# Sheet3.net
KiCad netlist of a schematic drawn in Altium Designer
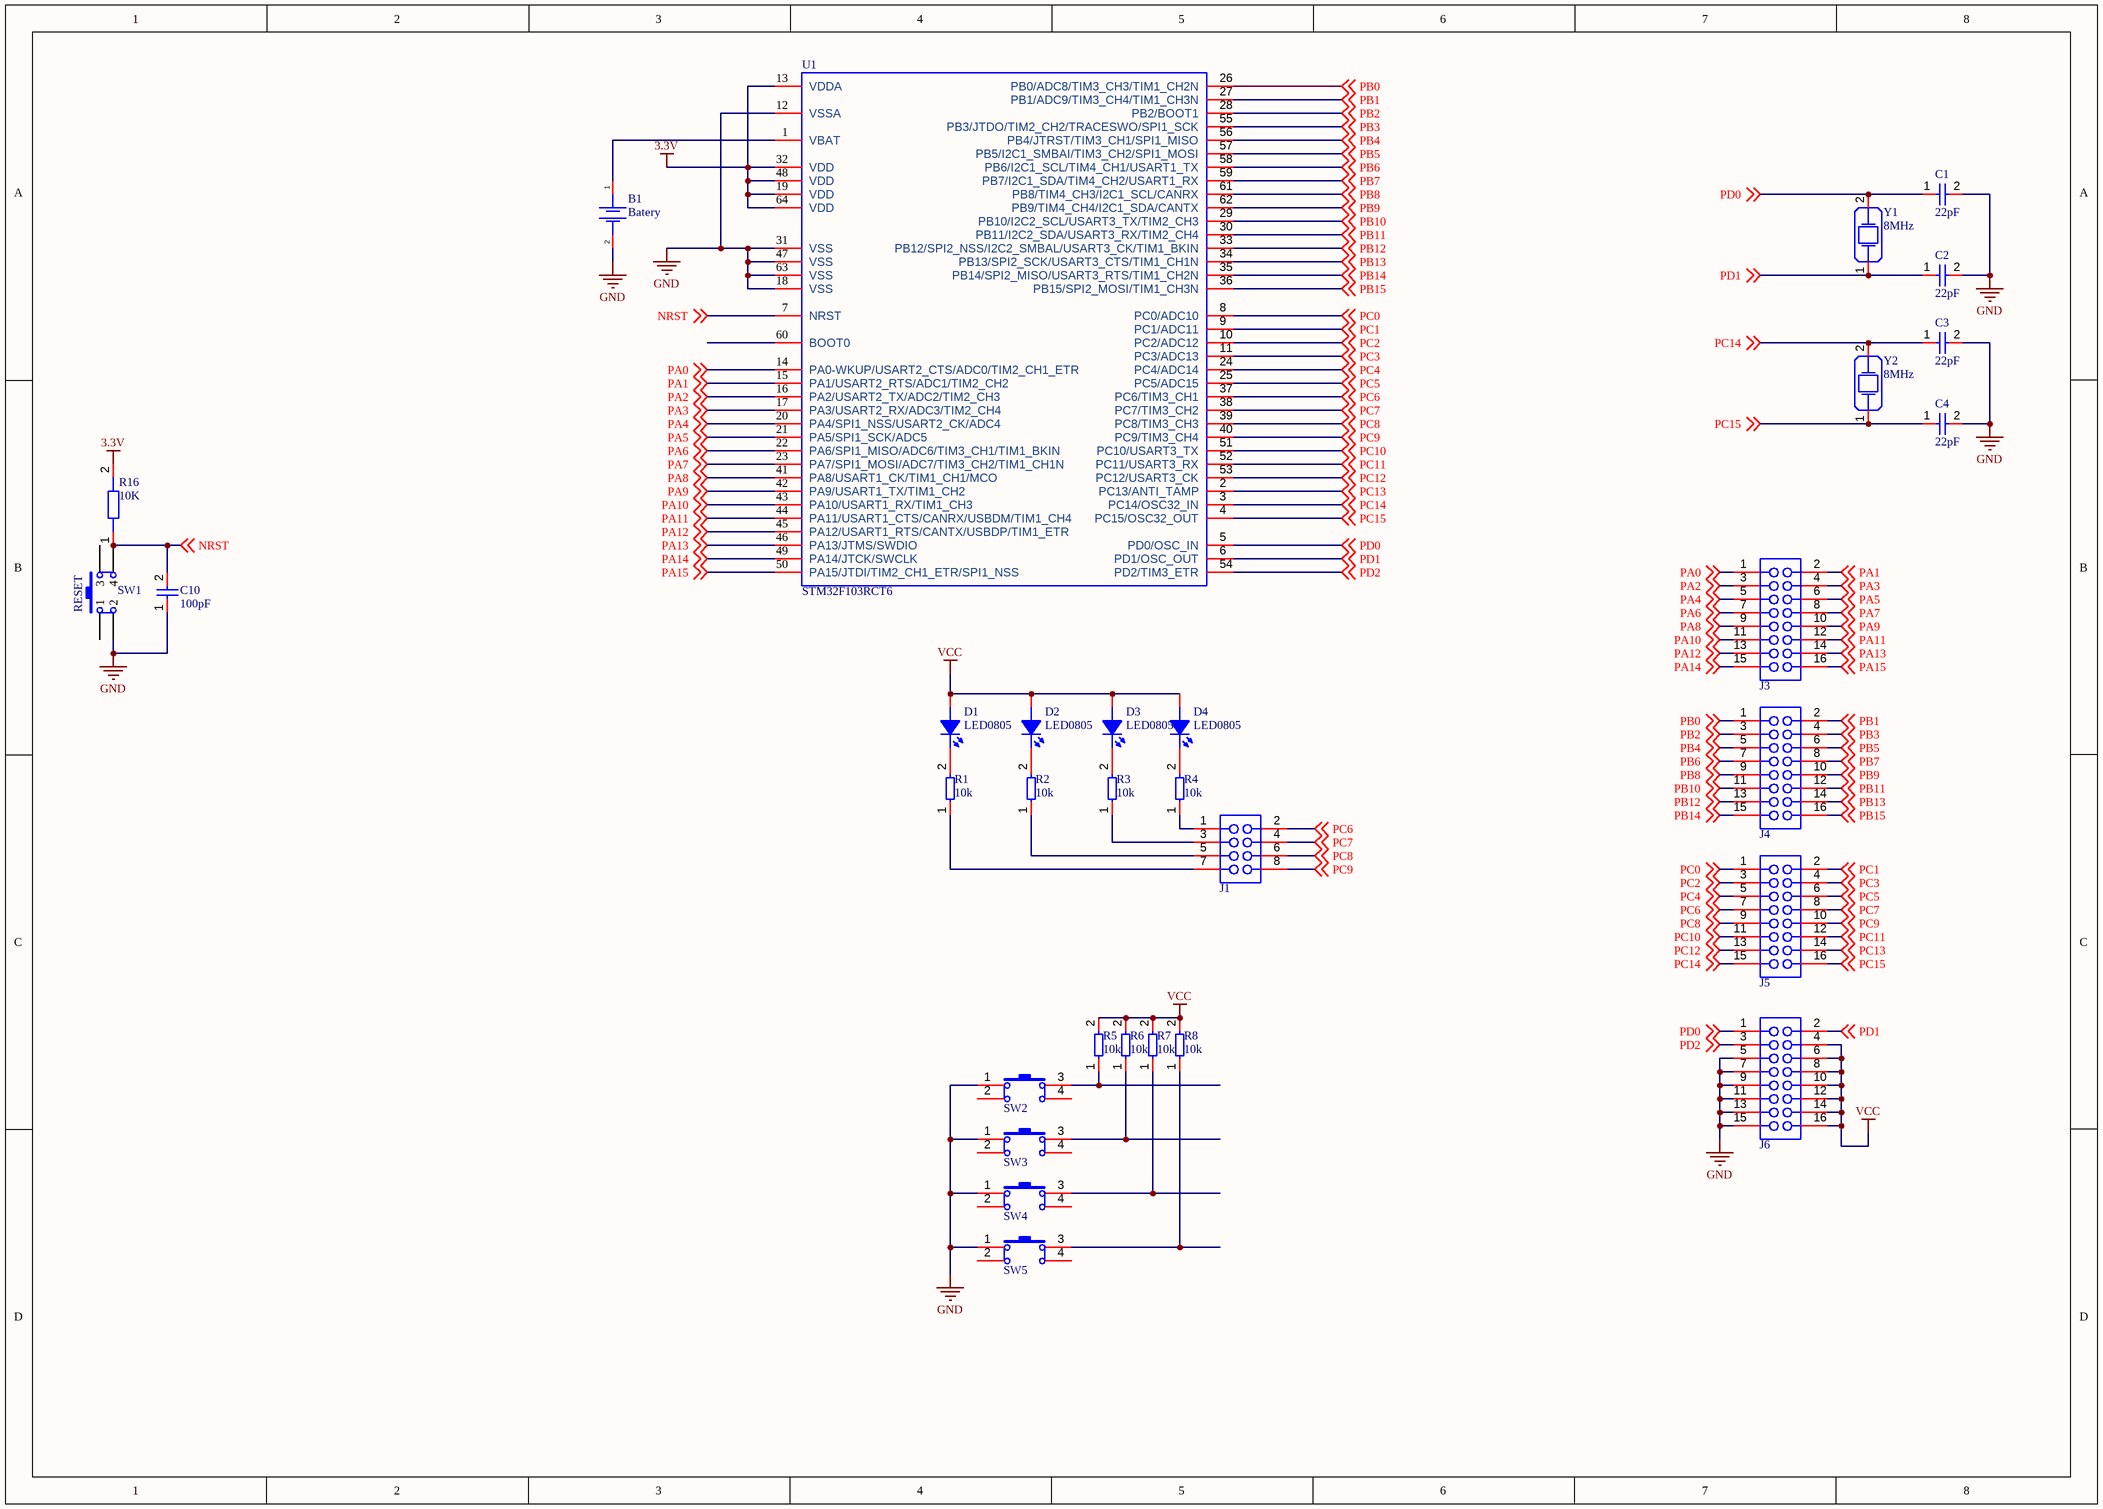
[diagram p0: Sheet3.SchDoc]

(export (version "E")
  (design (tool "Eeschema 10.0.6"))
  (components
    (comp (ref "B1") (value "Batery") (footprint "CR1220") (libsource (lib "SMDLibrary") (part "Batery")))
    (comp (ref "C1")
      (value "22pF")
      (footprint "C0805")
      (libsource (lib "SMDLibrary") (part "Capacitors(SMD)"))
    )
    (comp (ref "C2")
      (value "22pF")
      (footprint "C0805")
      (libsource (lib "SMDLibrary") (part "Capacitors(SMD)"))
    )
    (comp (ref "C3")
      (value "22pF")
      (footprint "C0805")
      (libsource (lib "SMDLibrary") (part "Capacitors(SMD)"))
    )
    (comp (ref "C4")
      (value "22pF")
      (footprint "C0805")
      (libsource (lib "SMDLibrary") (part "Capacitors(SMD)"))
    )
    (comp (ref "C10")
      (value "100pF")
      (footprint "CAP_DISC_PITCH_2.54MM")
      (libsource (lib "SMDLibrary") (part "Capacitors(Disc)"))
    )
    (comp (ref "D1") (value "LED0805") (footprint "L0805RED") (libsource (lib "SMDLibrary") (part "LED0805")))
    (comp (ref "D2") (value "LED0805") (footprint "L0805RED") (libsource (lib "SMDLibrary") (part "LED0805")))
    (comp (ref "D3") (value "LED0805") (footprint "L0805RED") (libsource (lib "SMDLibrary") (part "LED0805")))
    (comp (ref "D4") (value "LED0805") (footprint "L0805RED") (libsource (lib "SMDLibrary") (part "LED0805")))
    (comp (ref "J1")
      (value "Header 4x2 TH Pitch 2.54mm")
      (footprint "Header 4x2 TH Pitch 2.54mm")
      (libsource (lib "SMDLibrary") (part "Header 4x2 TH Pitch 2.54mm"))
    )
    (comp (ref "J3")
      (value "Header 8x2 TH Pitch 2.54mm")
      (footprint "Header 8x2 TH Pitch 2.54mm")
      (libsource (lib "SMDLibrary") (part "Header 8x2 TH Pitch 2.54mm"))
    )
    (comp (ref "J4")
      (value "Header 8x2 TH Pitch 2.54mm")
      (footprint "Header 8x2 TH Pitch 2.54mm")
      (libsource (lib "SMDLibrary") (part "Header 8x2 TH Pitch 2.54mm"))
    )
    (comp (ref "J5")
      (value "Header 8x2 TH Pitch 2.54mm")
      (footprint "Header 8x2 TH Pitch 2.54mm")
      (libsource (lib "SMDLibrary") (part "Header 8x2 TH Pitch 2.54mm"))
    )
    (comp (ref "J6")
      (value "Header 8x2 TH Pitch 2.54mm")
      (footprint "Header 8x2 TH Pitch 2.54mm")
      (libsource (lib "SMDLibrary") (part "Header 8x2 TH Pitch 2.54mm"))
    )
    (comp (ref "R1") (value "10k") (footprint "R0805") (libsource (lib "SMDLibrary") (part "Resistor SMD")))
    (comp (ref "R2") (value "10k") (footprint "R0805") (libsource (lib "SMDLibrary") (part "Resistor SMD")))
    (comp (ref "R3") (value "10k") (footprint "R0805") (libsource (lib "SMDLibrary") (part "Resistor SMD")))
    (comp (ref "R4") (value "10k") (footprint "R0805") (libsource (lib "SMDLibrary") (part "Resistor SMD")))
    (comp (ref "R5") (value "10k") (footprint "R0805") (libsource (lib "SMDLibrary") (part "Resistor SMD")))
    (comp (ref "R6") (value "10k") (footprint "R0805") (libsource (lib "SMDLibrary") (part "Resistor SMD")))
    (comp (ref "R7") (value "10k") (footprint "R0805") (libsource (lib "SMDLibrary") (part "Resistor SMD")))
    (comp (ref "R8") (value "10k") (footprint "R0805") (libsource (lib "SMDLibrary") (part "Resistor SMD")))
    (comp (ref "R16")
      (value "10K")
      (footprint "RES-0.25W-H-MF")
      (libsource (lib "SMDLibrary") (part "Resistors THD"))
    )
    (comp (ref "SW1")
      (value "RESET")
      (footprint "BUTTON_HOLE_5.0mm")
      (libsource (lib "SMDLibrary") (part "Button"))
    )
    (comp (ref "SW2")
      (value "Button1")
      (footprint "BUTTON_HOLE_5.0mm")
      (libsource (lib "SMDLibrary") (part "Button1"))
    )
    (comp (ref "SW3")
      (value "Button1")
      (footprint "BUTTON_HOLE_5.0mm")
      (libsource (lib "SMDLibrary") (part "Button1"))
    )
    (comp (ref "SW4")
      (value "Button1")
      (footprint "BUTTON_HOLE_5.0mm")
      (libsource (lib "SMDLibrary") (part "Button1"))
    )
    (comp (ref "SW5")
      (value "Button1")
      (footprint "BUTTON_HOLE_5.0mm")
      (libsource (lib "SMDLibrary") (part "Button1"))
    )
    (comp (ref "U1")
      (value "STM32F103RCT6")
      (footprint "QFP64_0.5 SOCKET PINOUT")
      (description "LQFP64")
      (libsource (lib "SMDLibrary") (part "STM32F103RCT6"))
    )
    (comp (ref "Y1") (value "8MHz") (footprint "SMD5032") (libsource (lib "SMDLibrary") (part "Crystal")))
    (comp (ref "Y2") (value "8MHz") (footprint "SMD5032") (libsource (lib "SMDLibrary") (part "Crystal")))
  )
  (nets
    (net (code "1") (name "3.3V") (class "Default")
      (node (ref "R16") (pin "2") (pinfunction "2_2") (pintype "passive"))
      (node (ref "U1") (pin "13") (pinfunction "VDDA_13") (pintype "passive"))
      (node (ref "U1") (pin "19") (pinfunction "VDD_19") (pintype "passive"))
      (node (ref "U1") (pin "32") (pinfunction "VDD_32") (pintype "passive"))
      (node (ref "U1") (pin "48") (pinfunction "VDD_48") (pintype "passive"))
      (node (ref "U1") (pin "64") (pinfunction "VDD_64") (pintype "passive"))
    )
    (net (code "2") (name "GND") (class "Default")
      (node (ref "B1") (pin "2") (pinfunction "2_2") (pintype "passive"))
      (node (ref "C1") (pin "2") (pinfunction "2_2") (pintype "passive"))
      (node (ref "C10") (pin "1") (pinfunction "1_1") (pintype "passive"))
      (node (ref "C2") (pin "2") (pinfunction "2_2") (pintype "passive"))
      (node (ref "C3") (pin "2") (pinfunction "2_2") (pintype "passive"))
      (node (ref "C4") (pin "2") (pinfunction "2_2") (pintype "passive"))
      (node (ref "J6") (pin "11") (pinfunction "11_11") (pintype "passive"))
      (node (ref "J6") (pin "13") (pinfunction "13_13") (pintype "passive"))
      (node (ref "J6") (pin "15") (pinfunction "15_15") (pintype "passive"))
      (node (ref "J6") (pin "5") (pinfunction "5_5") (pintype "passive"))
      (node (ref "J6") (pin "7") (pinfunction "7_7") (pintype "passive"))
      (node (ref "J6") (pin "9") (pinfunction "9_9") (pintype "passive"))
      (node (ref "SW1") (pin "2") (pinfunction "2_2") (pintype "passive"))
      (node (ref "SW2") (pin "1") (pinfunction "1_1") (pintype "passive"))
      (node (ref "SW3") (pin "1") (pinfunction "1_1") (pintype "passive"))
      (node (ref "SW4") (pin "1") (pinfunction "1_1") (pintype "passive"))
      (node (ref "SW5") (pin "1") (pinfunction "1_1") (pintype "passive"))
      (node (ref "U1") (pin "12") (pinfunction "VSSA_12") (pintype "passive"))
      (node (ref "U1") (pin "18") (pinfunction "VSS_18") (pintype "passive"))
      (node (ref "U1") (pin "31") (pinfunction "VSS_31") (pintype "passive"))
      (node (ref "U1") (pin "47") (pinfunction "VSS_47") (pintype "passive"))
      (node (ref "U1") (pin "63") (pinfunction "VSS_63") (pintype "passive"))
    )
    (net (code "3") (name "NRST") (class "Default")
      (node (ref "C10") (pin "2") (pinfunction "2_2") (pintype "passive"))
      (node (ref "R16") (pin "1") (pinfunction "1_1") (pintype "passive"))
      (node (ref "SW1") (pin "4") (pinfunction "4_4") (pintype "passive"))
      (node (ref "U1") (pin "7") (pinfunction "NRST_7") (pintype "passive"))
    )
    (net (code "4") (name "Net-(D1-K)") (class "Default")
      (node (ref "D1") (pin "2") (pinfunction "K_2") (pintype "passive"))
      (node (ref "R1") (pin "2") (pinfunction "2_2") (pintype "passive"))
    )
    (net (code "5") (name "Net-(D2-K)") (class "Default")
      (node (ref "D2") (pin "2") (pinfunction "K_2") (pintype "passive"))
      (node (ref "R2") (pin "2") (pinfunction "2_2") (pintype "passive"))
    )
    (net (code "6") (name "Net-(D3-K)") (class "Default")
      (node (ref "D3") (pin "2") (pinfunction "K_2") (pintype "passive"))
      (node (ref "R3") (pin "2") (pinfunction "2_2") (pintype "passive"))
    )
    (net (code "7") (name "Net-(D4-K)") (class "Default")
      (node (ref "D4") (pin "2") (pinfunction "K_2") (pintype "passive"))
      (node (ref "R4") (pin "2") (pinfunction "2_2") (pintype "passive"))
    )
    (net (code "8") (name "Net-(J1-Pad1)") (class "Default")
      (node (ref "J1") (pin "1") (pinfunction "1_1") (pintype "passive"))
      (node (ref "R4") (pin "1") (pinfunction "1_1") (pintype "passive"))
    )
    (net (code "9") (name "Net-(J1-Pad3)") (class "Default")
      (node (ref "J1") (pin "3") (pinfunction "3_3") (pintype "passive"))
      (node (ref "R3") (pin "1") (pinfunction "1_1") (pintype "passive"))
    )
    (net (code "10") (name "Net-(J1-Pad5)") (class "Default")
      (node (ref "J1") (pin "5") (pinfunction "5_5") (pintype "passive"))
      (node (ref "R2") (pin "1") (pinfunction "1_1") (pintype "passive"))
    )
    (net (code "11") (name "Net-(J1-Pad7)") (class "Default")
      (node (ref "J1") (pin "7") (pinfunction "7_7") (pintype "passive"))
      (node (ref "R1") (pin "1") (pinfunction "1_1") (pintype "passive"))
    )
    (net (code "12") (name "Net-(R5-Pad1)") (class "Default")
      (node (ref "R5") (pin "1") (pinfunction "1_1") (pintype "passive"))
      (node (ref "SW2") (pin "3") (pinfunction "3_3") (pintype "passive"))
    )
    (net (code "13") (name "Net-(R6-Pad1)") (class "Default")
      (node (ref "R6") (pin "1") (pinfunction "1_1") (pintype "passive"))
      (node (ref "SW3") (pin "3") (pinfunction "3_3") (pintype "passive"))
    )
    (net (code "14") (name "Net-(R7-Pad1)") (class "Default")
      (node (ref "R7") (pin "1") (pinfunction "1_1") (pintype "passive"))
      (node (ref "SW4") (pin "3") (pinfunction "3_3") (pintype "passive"))
    )
    (net (code "15") (name "Net-(R8-Pad1)") (class "Default")
      (node (ref "R8") (pin "1") (pinfunction "1_1") (pintype "passive"))
      (node (ref "SW5") (pin "3") (pinfunction "3_3") (pintype "passive"))
    )
    (net (code "16") (name "Net-(U1-VBAT)") (class "Default")
      (node (ref "B1") (pin "1") (pinfunction "1_1") (pintype "passive"))
      (node (ref "U1") (pin "1") (pinfunction "VBAT_1") (pintype "passive"))
    )
    (net (code "17") (name "PA0") (class "Default")
      (node (ref "J3") (pin "1") (pinfunction "1_1") (pintype "passive"))
      (node (ref "U1") (pin "14") (pinfunction "PA0-WKUP/USART2_CTS/ADC0/TIM2_CH1_ETR_14") (pintype "passive"))
    )
    (net (code "18") (name "PA1") (class "Default")
      (node (ref "J3") (pin "2") (pinfunction "2_2") (pintype "passive"))
      (node (ref "U1") (pin "15") (pinfunction "PA1/USART2_RTS/ADC1/TIM2_CH2_15") (pintype "passive"))
    )
    (net (code "19") (name "PA2") (class "Default")
      (node (ref "J3") (pin "3") (pinfunction "3_3") (pintype "passive"))
      (node (ref "U1") (pin "16") (pinfunction "PA2/USART2_TX/ADC2/TIM2_CH3_16") (pintype "passive"))
    )
    (net (code "20") (name "PA3") (class "Default")
      (node (ref "J3") (pin "4") (pinfunction "4_4") (pintype "passive"))
      (node (ref "U1") (pin "17") (pinfunction "PA3/USART2_RX/ADC3/TIM2_CH4_17") (pintype "passive"))
    )
    (net (code "21") (name "PA4") (class "Default")
      (node (ref "J3") (pin "5") (pinfunction "5_5") (pintype "passive"))
      (node (ref "U1") (pin "20") (pinfunction "PA4/SPI1_NSS/USART2_CK/ADC4_20") (pintype "passive"))
    )
    (net (code "22") (name "PA5") (class "Default")
      (node (ref "J3") (pin "6") (pinfunction "6_6") (pintype "passive"))
      (node (ref "U1") (pin "21") (pinfunction "PA5/SPI1_SCK/ADC5_21") (pintype "passive"))
    )
    (net (code "23") (name "PA6") (class "Default")
      (node (ref "J3") (pin "7") (pinfunction "7_7") (pintype "passive"))
      (node (ref "U1") (pin "22") (pinfunction "PA6/SPI1_MISO/ADC6/TIM3_CH1/TIM1_BKIN_22") (pintype "passive"))
    )
    (net (code "24") (name "PA7") (class "Default")
      (node (ref "J3") (pin "8") (pinfunction "8_8") (pintype "passive"))
      (node (ref "U1") (pin "23") (pinfunction "PA7/SPI1_MOSI/ADC7/TIM3_CH2/TIM1_CH1N_23") (pintype "passive"))
    )
    (net (code "25") (name "PA8") (class "Default")
      (node (ref "J3") (pin "9") (pinfunction "9_9") (pintype "passive"))
      (node (ref "U1") (pin "41") (pinfunction "PA8/USART1_CK/TIM1_CH1/MCO_41") (pintype "passive"))
    )
    (net (code "26") (name "PA9") (class "Default")
      (node (ref "J3") (pin "10") (pinfunction "10_10") (pintype "passive"))
      (node (ref "U1") (pin "42") (pinfunction "PA9/USART1_TX/TIM1_CH2_42") (pintype "passive"))
    )
    (net (code "27") (name "PA10") (class "Default")
      (node (ref "J3") (pin "11") (pinfunction "11_11") (pintype "passive"))
      (node (ref "U1") (pin "43") (pinfunction "PA10/USART1_RX/TIM1_CH3_43") (pintype "passive"))
    )
    (net (code "28") (name "PA11") (class "Default")
      (node (ref "J3") (pin "12") (pinfunction "12_12") (pintype "passive"))
      (node (ref "U1") (pin "44") (pinfunction "PA11/USART1_CTS/CANRX/USBDM/TIM1_CH4_44") (pintype "passive"))
    )
    (net (code "29") (name "PA12") (class "Default")
      (node (ref "J3") (pin "13") (pinfunction "13_13") (pintype "passive"))
      (node (ref "U1") (pin "45") (pinfunction "PA12/USART1_RTS/CANTX/USBDP/TIM1_ETR_45") (pintype "passive"))
    )
    (net (code "30") (name "PA13") (class "Default")
      (node (ref "J3") (pin "14") (pinfunction "14_14") (pintype "passive"))
      (node (ref "U1") (pin "46") (pinfunction "PA13/JTMS/SWDIO_46") (pintype "passive"))
    )
    (net (code "31") (name "PA14") (class "Default")
      (node (ref "J3") (pin "15") (pinfunction "15_15") (pintype "passive"))
      (node (ref "U1") (pin "49") (pinfunction "PA14/JTCK/SWCLK_49") (pintype "passive"))
    )
    (net (code "32") (name "PA15") (class "Default")
      (node (ref "J3") (pin "16") (pinfunction "16_16") (pintype "passive"))
      (node (ref "U1") (pin "50") (pinfunction "PA15/JTDI/TIM2_CH1_ETR/SPI1_NSS_50") (pintype "passive"))
    )
    (net (code "33") (name "PB0") (class "Default")
      (node (ref "J4") (pin "1") (pinfunction "1_1") (pintype "passive"))
      (node (ref "U1") (pin "26") (pinfunction "PB0/ADC8/TIM3_CH3/TIM1_CH2N_26") (pintype "passive"))
    )
    (net (code "34") (name "PB1") (class "Default")
      (node (ref "J4") (pin "2") (pinfunction "2_2") (pintype "passive"))
      (node (ref "U1") (pin "27") (pinfunction "PB1/ADC9/TIM3_CH4/TIM1_CH3N_27") (pintype "passive"))
    )
    (net (code "35") (name "PB2") (class "Default")
      (node (ref "J4") (pin "3") (pinfunction "3_3") (pintype "passive"))
      (node (ref "U1") (pin "28") (pinfunction "PB2/BOOT1_28") (pintype "passive"))
    )
    (net (code "36") (name "PB3") (class "Default")
      (node (ref "J4") (pin "4") (pinfunction "4_4") (pintype "passive"))
      (node (ref "U1") (pin "55") (pinfunction "PB3/JTDO/TIM2_CH2/TRACESWO/SPI1_SCK_55") (pintype "passive"))
    )
    (net (code "37") (name "PB4") (class "Default")
      (node (ref "J4") (pin "5") (pinfunction "5_5") (pintype "passive"))
      (node (ref "U1") (pin "56") (pinfunction "PB4/JTRST/TIM3_CH1/SPI1_MISO_56") (pintype "passive"))
    )
    (net (code "38") (name "PB5") (class "Default")
      (node (ref "J4") (pin "6") (pinfunction "6_6") (pintype "passive"))
      (node (ref "U1") (pin "57") (pinfunction "PB5/I2C1_SMBAI/TIM3_CH2/SPI1_MOSI_57") (pintype "passive"))
    )
    (net (code "39") (name "PB6") (class "Default")
      (node (ref "J4") (pin "7") (pinfunction "7_7") (pintype "passive"))
      (node (ref "U1") (pin "58") (pinfunction "PB6/I2C1_SCL/TIM4_CH1/USART1_TX_58") (pintype "passive"))
    )
    (net (code "40") (name "PB7") (class "Default")
      (node (ref "J4") (pin "8") (pinfunction "8_8") (pintype "passive"))
      (node (ref "U1") (pin "59") (pinfunction "PB7/I2C1_SDA/TIM4_CH2/USART1_RX_59") (pintype "passive"))
    )
    (net (code "41") (name "PB8") (class "Default")
      (node (ref "J4") (pin "9") (pinfunction "9_9") (pintype "passive"))
      (node (ref "U1") (pin "61") (pinfunction "PB8/TIM4_CH3/I2C1_SCL/CANRX_61") (pintype "passive"))
    )
    (net (code "42") (name "PB9") (class "Default")
      (node (ref "J4") (pin "10") (pinfunction "10_10") (pintype "passive"))
      (node (ref "U1") (pin "62") (pinfunction "PB9/TIM4_CH4/I2C1_SDA/CANTX_62") (pintype "passive"))
    )
    (net (code "43") (name "PB10") (class "Default")
      (node (ref "J4") (pin "11") (pinfunction "11_11") (pintype "passive"))
      (node (ref "U1") (pin "29") (pinfunction "PB10/I2C2_SCL/USART3_TX/TIM2_CH3_29") (pintype "passive"))
    )
    (net (code "44") (name "PB11") (class "Default")
      (node (ref "J4") (pin "12") (pinfunction "12_12") (pintype "passive"))
      (node (ref "U1") (pin "30") (pinfunction "PB11/I2C2_SDA/USART3_RX/TIM2_CH4_30") (pintype "passive"))
    )
    (net (code "45") (name "PB12") (class "Default")
      (node (ref "J4") (pin "13") (pinfunction "13_13") (pintype "passive"))
      (node (ref "U1") (pin "33") (pinfunction "PB12/SPI2_NSS/I2C2_SMBAL/USART3_CK/TIM1_BKIN_33") (pintype "passive"))
    )
    (net (code "46") (name "PB13") (class "Default")
      (node (ref "J4") (pin "14") (pinfunction "14_14") (pintype "passive"))
      (node (ref "U1") (pin "34") (pinfunction "PB13/SPI2_SCK/USART3_CTS/TIM1_CH1N_34") (pintype "passive"))
    )
    (net (code "47") (name "PB14") (class "Default")
      (node (ref "J4") (pin "15") (pinfunction "15_15") (pintype "passive"))
      (node (ref "U1") (pin "35") (pinfunction "PB14/SPI2_MISO/USART3_RTS/TIM1_CH2N_35") (pintype "passive"))
    )
    (net (code "48") (name "PB15") (class "Default")
      (node (ref "J4") (pin "16") (pinfunction "16_16") (pintype "passive"))
      (node (ref "U1") (pin "36") (pinfunction "PB15/SPI2_MOSI/TIM1_CH3N_36") (pintype "passive"))
    )
    (net (code "49") (name "PC0") (class "Default")
      (node (ref "J5") (pin "1") (pinfunction "1_1") (pintype "passive"))
      (node (ref "U1") (pin "8") (pinfunction "PC0/ADC10_8") (pintype "passive"))
    )
    (net (code "50") (name "PC1") (class "Default")
      (node (ref "J5") (pin "2") (pinfunction "2_2") (pintype "passive"))
      (node (ref "U1") (pin "9") (pinfunction "PC1/ADC11_9") (pintype "passive"))
    )
    (net (code "51") (name "PC2") (class "Default")
      (node (ref "J5") (pin "3") (pinfunction "3_3") (pintype "passive"))
      (node (ref "U1") (pin "10") (pinfunction "PC2/ADC12_10") (pintype "passive"))
    )
    (net (code "52") (name "PC3") (class "Default")
      (node (ref "J5") (pin "4") (pinfunction "4_4") (pintype "passive"))
      (node (ref "U1") (pin "11") (pinfunction "PC3/ADC13_11") (pintype "passive"))
    )
    (net (code "53") (name "PC4") (class "Default")
      (node (ref "J5") (pin "5") (pinfunction "5_5") (pintype "passive"))
      (node (ref "U1") (pin "24") (pinfunction "PC4/ADC14_24") (pintype "passive"))
    )
    (net (code "54") (name "PC5") (class "Default")
      (node (ref "J5") (pin "6") (pinfunction "6_6") (pintype "passive"))
      (node (ref "U1") (pin "25") (pinfunction "PC5/ADC15_25") (pintype "passive"))
    )
    (net (code "55") (name "PC6") (class "Default")
      (node (ref "J1") (pin "2") (pinfunction "2_2") (pintype "passive"))
      (node (ref "J5") (pin "7") (pinfunction "7_7") (pintype "passive"))
      (node (ref "U1") (pin "37") (pinfunction "PC6/TIM3_CH1_37") (pintype "passive"))
    )
    (net (code "56") (name "PC7") (class "Default")
      (node (ref "J1") (pin "4") (pinfunction "4_4") (pintype "passive"))
      (node (ref "J5") (pin "8") (pinfunction "8_8") (pintype "passive"))
      (node (ref "U1") (pin "38") (pinfunction "PC7/TIM3_CH2_38") (pintype "passive"))
    )
    (net (code "57") (name "PC8") (class "Default")
      (node (ref "J1") (pin "6") (pinfunction "6_6") (pintype "passive"))
      (node (ref "J5") (pin "9") (pinfunction "9_9") (pintype "passive"))
      (node (ref "U1") (pin "39") (pinfunction "PC8/TIM3_CH3_39") (pintype "passive"))
    )
    (net (code "58") (name "PC9") (class "Default")
      (node (ref "J1") (pin "8") (pinfunction "8_8") (pintype "passive"))
      (node (ref "J5") (pin "10") (pinfunction "10_10") (pintype "passive"))
      (node (ref "U1") (pin "40") (pinfunction "PC9/TIM3_CH4_40") (pintype "passive"))
    )
    (net (code "59") (name "PC10") (class "Default")
      (node (ref "J5") (pin "11") (pinfunction "11_11") (pintype "passive"))
      (node (ref "U1") (pin "51") (pinfunction "PC10/USART3_TX_51") (pintype "passive"))
    )
    (net (code "60") (name "PC11") (class "Default")
      (node (ref "J5") (pin "12") (pinfunction "12_12") (pintype "passive"))
      (node (ref "U1") (pin "52") (pinfunction "PC11/USART3_RX_52") (pintype "passive"))
    )
    (net (code "61") (name "PC12") (class "Default")
      (node (ref "J5") (pin "13") (pinfunction "13_13") (pintype "passive"))
      (node (ref "U1") (pin "53") (pinfunction "PC12/USART3_CK_53") (pintype "passive"))
    )
    (net (code "62") (name "PC13") (class "Default")
      (node (ref "J5") (pin "14") (pinfunction "14_14") (pintype "passive"))
      (node (ref "U1") (pin "2") (pinfunction "PC13/ANTI_TAMP_2") (pintype "passive"))
    )
    (net (code "63") (name "PC14") (class "Default")
      (node (ref "C3") (pin "1") (pinfunction "1_1") (pintype "passive"))
      (node (ref "J5") (pin "15") (pinfunction "15_15") (pintype "passive"))
      (node (ref "U1") (pin "3") (pinfunction "PC14/OSC32_IN_3") (pintype "passive"))
      (node (ref "Y2") (pin "2") (pinfunction "2_2") (pintype "passive"))
    )
    (net (code "64") (name "PC15") (class "Default")
      (node (ref "C4") (pin "1") (pinfunction "1_1") (pintype "passive"))
      (node (ref "J5") (pin "16") (pinfunction "16_16") (pintype "passive"))
      (node (ref "U1") (pin "4") (pinfunction "PC15/OSC32_OUT_4") (pintype "passive"))
      (node (ref "Y2") (pin "1") (pinfunction "1_1") (pintype "passive"))
    )
    (net (code "65") (name "PD0") (class "Default")
      (node (ref "C1") (pin "1") (pinfunction "1_1") (pintype "passive"))
      (node (ref "J6") (pin "1") (pinfunction "1_1") (pintype "passive"))
      (node (ref "U1") (pin "5") (pinfunction "PD0/OSC_IN_5") (pintype "passive"))
      (node (ref "Y1") (pin "2") (pinfunction "2_2") (pintype "passive"))
    )
    (net (code "66") (name "PD1") (class "Default")
      (node (ref "C2") (pin "1") (pinfunction "1_1") (pintype "passive"))
      (node (ref "J6") (pin "2") (pinfunction "2_2") (pintype "passive"))
      (node (ref "U1") (pin "6") (pinfunction "PD1/OSC_OUT_6") (pintype "passive"))
      (node (ref "Y1") (pin "1") (pinfunction "1_1") (pintype "passive"))
    )
    (net (code "67") (name "PD2") (class "Default")
      (node (ref "J6") (pin "3") (pinfunction "3_3") (pintype "passive"))
      (node (ref "U1") (pin "54") (pinfunction "PD2/TIM3_ETR_54") (pintype "passive"))
    )
    (net (code "68") (name "VCC") (class "Default")
      (node (ref "D1") (pin "1") (pinfunction "A_1") (pintype "passive"))
      (node (ref "D2") (pin "1") (pinfunction "A_1") (pintype "passive"))
      (node (ref "D3") (pin "1") (pinfunction "A_1") (pintype "passive"))
      (node (ref "D4") (pin "1") (pinfunction "A_1") (pintype "passive"))
      (node (ref "J6") (pin "10") (pinfunction "10_10") (pintype "passive"))
      (node (ref "J6") (pin "12") (pinfunction "12_12") (pintype "passive"))
      (node (ref "J6") (pin "14") (pinfunction "14_14") (pintype "passive"))
      (node (ref "J6") (pin "16") (pinfunction "16_16") (pintype "passive"))
      (node (ref "J6") (pin "4") (pinfunction "4_4") (pintype "passive"))
      (node (ref "J6") (pin "6") (pinfunction "6_6") (pintype "passive"))
      (node (ref "J6") (pin "8") (pinfunction "8_8") (pintype "passive"))
      (node (ref "R5") (pin "2") (pinfunction "2_2") (pintype "passive"))
      (node (ref "R6") (pin "2") (pinfunction "2_2") (pintype "passive"))
      (node (ref "R7") (pin "2") (pinfunction "2_2") (pintype "passive"))
      (node (ref "R8") (pin "2") (pinfunction "2_2") (pintype "passive"))
    )
    (net (code "69") (name "unconnected-(SW1-Pad1)") (class "Default")
      (node (ref "SW1") (pin "1") (pinfunction "1_1") (pintype "passive"))
    )
    (net (code "70") (name "unconnected-(SW1-Pad3)") (class "Default")
      (node (ref "SW1") (pin "3") (pinfunction "3_3") (pintype "passive"))
    )
    (net (code "71") (name "unconnected-(SW2-Pad2)") (class "Default")
      (node (ref "SW2") (pin "2") (pinfunction "2_2") (pintype "passive"))
    )
    (net (code "72") (name "unconnected-(SW2-Pad4)") (class "Default")
      (node (ref "SW2") (pin "4") (pinfunction "4_4") (pintype "passive"))
    )
    (net (code "73") (name "unconnected-(SW3-Pad2)") (class "Default")
      (node (ref "SW3") (pin "2") (pinfunction "2_2") (pintype "passive"))
    )
    (net (code "74") (name "unconnected-(SW3-Pad4)") (class "Default")
      (node (ref "SW3") (pin "4") (pinfunction "4_4") (pintype "passive"))
    )
    (net (code "75") (name "unconnected-(SW4-Pad2)") (class "Default")
      (node (ref "SW4") (pin "2") (pinfunction "2_2") (pintype "passive"))
    )
    (net (code "76") (name "unconnected-(SW4-Pad4)") (class "Default")
      (node (ref "SW4") (pin "4") (pinfunction "4_4") (pintype "passive"))
    )
    (net (code "77") (name "unconnected-(SW5-Pad2)") (class "Default")
      (node (ref "SW5") (pin "2") (pinfunction "2_2") (pintype "passive"))
    )
    (net (code "78") (name "unconnected-(SW5-Pad4)") (class "Default")
      (node (ref "SW5") (pin "4") (pinfunction "4_4") (pintype "passive"))
    )
    (net (code "79") (name "unconnected-(U1-BOOT0-Pad60)") (class "Default")
      (node (ref "U1") (pin "60") (pinfunction "BOOT0_60") (pintype "passive"))
    )
  )
)
